# D5035-51.net
KiCad netlist of a schematic drawn in Altium Designer
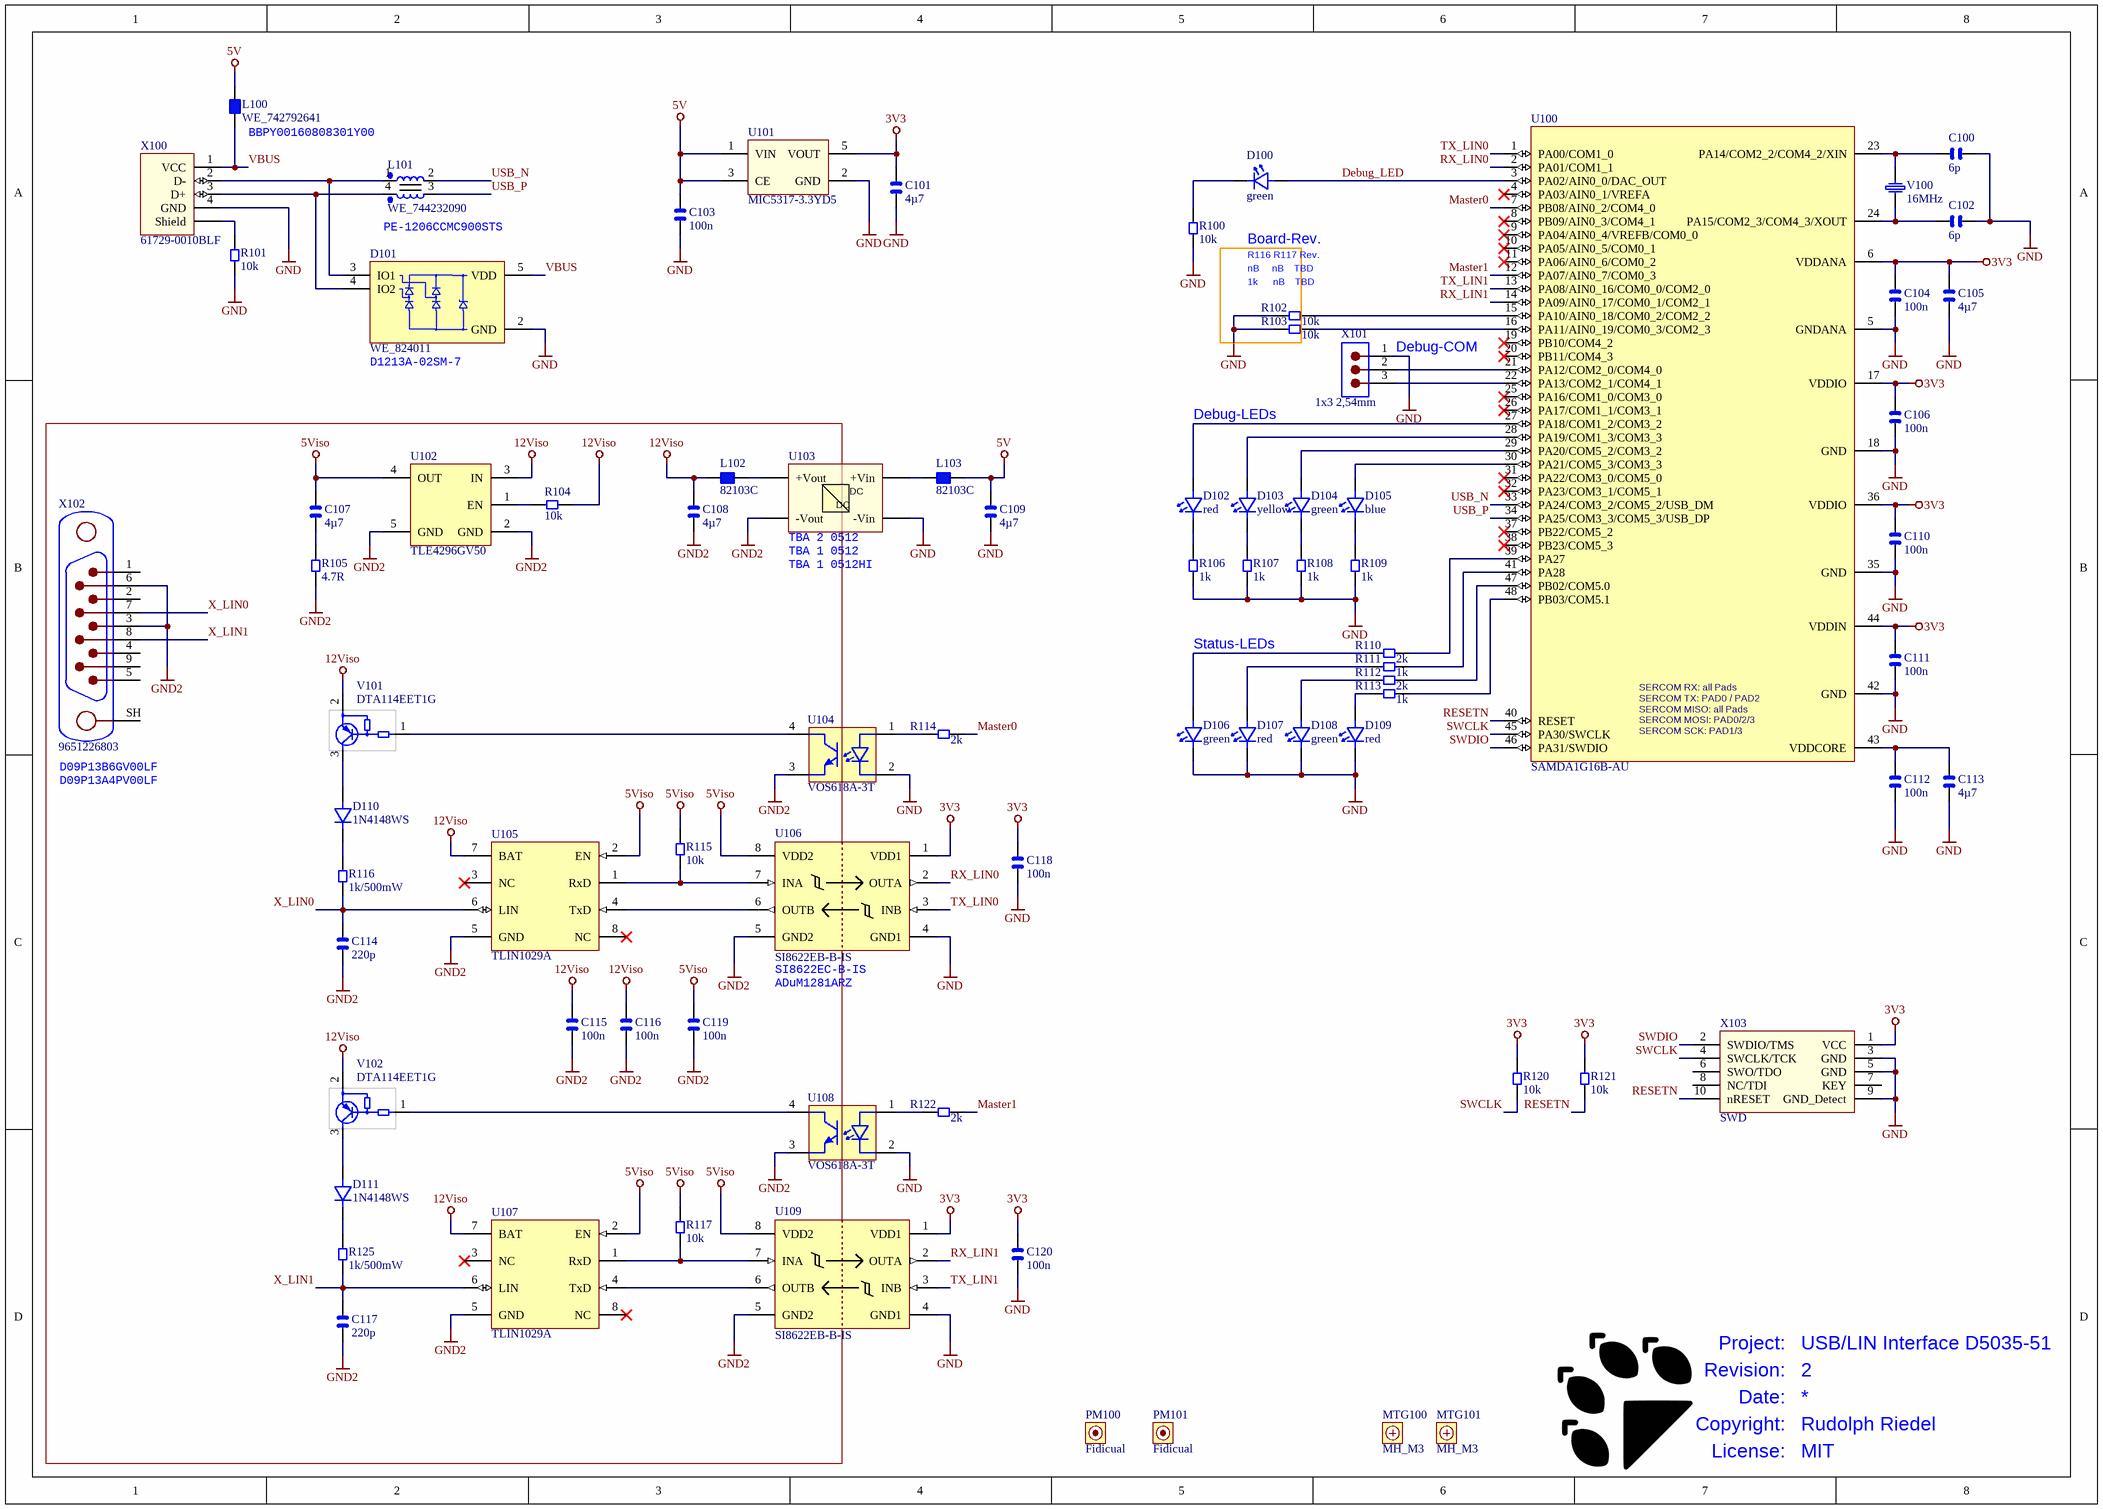
[diagram p0: D5035-51.SchDoc]

(export (version "E")
  (design (tool "Eeschema 10.0.6"))
  (components
    (comp (ref "C100")
      (value "6p")
      (footprint "CAPC1608X09L")
      (description "0603 Chip Capacitor")
      (fields (field (name "PART NUMBER") "CAPC_0603") (field (name "EDITOR") "rriedel"))
      (libsource (lib "HW-Labor_GF") (part "CAP_2_V2"))
    )
    (comp (ref "C101")
      (value "4µ7")
      (footprint "CAPC2012X14L")
      (description "0805 Chip Capacitor")
      (fields (field (name "PART NUMBER") "CAPC_0805") (field (name "EDITOR") "rriedel"))
      (libsource (lib "HW-Labor_GF") (part "CAP_2_V2"))
    )
    (comp (ref "C102")
      (value "6p")
      (footprint "CAPC1608X09L")
      (description "0603 Chip Capacitor")
      (fields (field (name "PART NUMBER") "CAPC_0603") (field (name "EDITOR") "rriedel"))
      (libsource (lib "HW-Labor_GF") (part "CAP_2_V2"))
    )
    (comp (ref "C103")
      (value "100n")
      (footprint "CAPC1608X09L")
      (description "0603 Chip Capacitor")
      (fields (field (name "PART NUMBER") "CAPC_0603") (field (name "EDITOR") "rriedel"))
      (libsource (lib "HW-Labor_GF") (part "CAP_2_V2"))
    )
    (comp (ref "C104")
      (value "100n")
      (footprint "CAPC1608X09L")
      (description "0603 Chip Capacitor")
      (fields (field (name "PART NUMBER") "CAPC_0603") (field (name "EDITOR") "rriedel"))
      (libsource (lib "HW-Labor_GF") (part "CAP_2_V2"))
    )
    (comp (ref "C105")
      (value "4µ7")
      (footprint "CAPC2012X14L")
      (description "0805 Chip Capacitor")
      (fields (field (name "PART NUMBER") "CAPC_0805") (field (name "EDITOR") "rriedel"))
      (libsource (lib "HW-Labor_GF") (part "CAP_2_V2"))
    )
    (comp (ref "C106")
      (value "100n")
      (footprint "CAPC1608X09L")
      (description "0603 Chip Capacitor")
      (fields (field (name "PART NUMBER") "CAPC_0603") (field (name "EDITOR") "rriedel"))
      (libsource (lib "HW-Labor_GF") (part "CAP_2_V2"))
    )
    (comp (ref "C107")
      (value "4µ7")
      (footprint "CAPC2012X14L")
      (description "0805 Chip Capacitor")
      (fields (field (name "PART NUMBER") "CAPC_0805") (field (name "EDITOR") "rriedel"))
      (libsource (lib "HW-Labor_GF") (part "CAP_2_V2"))
    )
    (comp (ref "C108")
      (value "4µ7")
      (footprint "CAPC2012X14L")
      (description "0805 Chip Capacitor")
      (fields (field (name "PART NUMBER") "CAPC_0805") (field (name "EDITOR") "rriedel"))
      (libsource (lib "HW-Labor_GF") (part "CAP_2_V2"))
    )
    (comp (ref "C109")
      (value "4µ7")
      (footprint "CAPC2012X14L")
      (description "0805 Chip Capacitor")
      (fields (field (name "PART NUMBER") "CAPC_0805") (field (name "EDITOR") "rriedel"))
      (libsource (lib "HW-Labor_GF") (part "CAP_2_V2"))
    )
    (comp (ref "C110")
      (value "100n")
      (footprint "CAPC1608X09L")
      (description "0603 Chip Capacitor")
      (fields (field (name "PART NUMBER") "CAPC_0603") (field (name "EDITOR") "rriedel"))
      (libsource (lib "HW-Labor_GF") (part "CAP_2_V2"))
    )
    (comp (ref "C111")
      (value "100n")
      (footprint "CAPC1608X09L")
      (description "0603 Chip Capacitor")
      (fields (field (name "PART NUMBER") "CAPC_0603") (field (name "EDITOR") "rriedel"))
      (libsource (lib "HW-Labor_GF") (part "CAP_2_V2"))
    )
    (comp (ref "C112")
      (value "100n")
      (footprint "CAPC1608X09L")
      (description "0603 Chip Capacitor")
      (fields (field (name "PART NUMBER") "CAPC_0603") (field (name "EDITOR") "rriedel"))
      (libsource (lib "HW-Labor_GF") (part "CAP_2_V2"))
    )
    (comp (ref "C113")
      (value "4µ7")
      (footprint "CAPC2012X14L")
      (description "0805 Chip Capacitor")
      (fields (field (name "PART NUMBER") "CAPC_0805") (field (name "EDITOR") "rriedel"))
      (libsource (lib "HW-Labor_GF") (part "CAP_2_V2"))
    )
    (comp (ref "C114")
      (value "220p")
      (footprint "CAPC2012X14L")
      (description "0805 Chip Capacitor")
      (fields (field (name "PART NUMBER") "CAPC_0805") (field (name "EDITOR") "rriedel"))
      (libsource (lib "HW-Labor_GF") (part "CAP_2_V2"))
    )
    (comp (ref "C115")
      (value "100n")
      (footprint "CAPC1608X09L")
      (description "0603 Chip Capacitor")
      (fields (field (name "PART NUMBER") "CAPC_0603") (field (name "EDITOR") "rriedel"))
      (libsource (lib "HW-Labor_GF") (part "CAP_2_V2"))
    )
    (comp (ref "C116")
      (value "100n")
      (footprint "CAPC1608X09L")
      (description "0603 Chip Capacitor")
      (fields (field (name "PART NUMBER") "CAPC_0603") (field (name "EDITOR") "rriedel"))
      (libsource (lib "HW-Labor_GF") (part "CAP_2_V2"))
    )
    (comp (ref "C117")
      (value "220p")
      (footprint "CAPC2012X14L")
      (description "0805 Chip Capacitor")
      (fields (field (name "PART NUMBER") "CAPC_0805") (field (name "EDITOR") "rriedel"))
      (libsource (lib "HW-Labor_GF") (part "CAP_2_V2"))
    )
    (comp (ref "C118")
      (value "100n")
      (footprint "CAPC1608X09L")
      (description "0603 Chip Capacitor")
      (fields (field (name "PART NUMBER") "CAPC_0603") (field (name "EDITOR") "rriedel"))
      (libsource (lib "HW-Labor_GF") (part "CAP_2_V2"))
    )
    (comp (ref "C119")
      (value "100n")
      (footprint "CAPC1608X09L")
      (description "0603 Chip Capacitor")
      (fields (field (name "PART NUMBER") "CAPC_0603") (field (name "EDITOR") "rriedel"))
      (libsource (lib "HW-Labor_GF") (part "CAP_2_V2"))
    )
    (comp (ref "C120")
      (value "100n")
      (footprint "CAPC1608X09L")
      (description "0603 Chip Capacitor")
      (fields (field (name "PART NUMBER") "CAPC_0603") (field (name "EDITOR") "rriedel"))
      (libsource (lib "HW-Labor_GF") (part "CAP_2_V2"))
    )
    (comp (ref "D100")
      (value "green")
      (footprint "DIOC1608X06N_LED")
      (description "LED, 0603")
      (fields (field (name "PART NUMBER") "LED_0603") (field (name "EDITOR") "rriedel"))
      (libsource (lib "HW-Labor_GF") (part "LED_generic"))
    )
    (comp (ref "D101")
      (value "WE_824011")
      (footprint "SOT95P280X110-5N")
      (description "TVS Diode Array WE-TVS")
      (fields
        (field (name "MANUFACTURER") "Wuerth")
        (field (name "DISTRIBUTOR_1_PART_NUMBER") "732-4465-1-ND")
        (field (name "EDITOR") "rriedel")
      )
      (libsource (lib "HW-Labor_GF") (part "WE-824011"))
    )
    (comp (ref "D102")
      (value "red")
      (footprint "DIOC1608X06N_LED")
      (description "LED, 0603")
      (fields (field (name "PART NUMBER") "LED_0603") (field (name "EDITOR") "rriedel"))
      (libsource (lib "HW-Labor_GF") (part "LED_generic"))
    )
    (comp (ref "D103")
      (value "yellow")
      (footprint "DIOC1608X06N_LED")
      (description "LED, 0603")
      (fields (field (name "PART NUMBER") "LED_0603") (field (name "EDITOR") "rriedel"))
      (libsource (lib "HW-Labor_GF") (part "LED_generic"))
    )
    (comp (ref "D104")
      (value "green")
      (footprint "DIOC1608X06N_LED")
      (description "LED, 0603")
      (fields (field (name "PART NUMBER") "LED_0603") (field (name "EDITOR") "rriedel"))
      (libsource (lib "HW-Labor_GF") (part "LED_generic"))
    )
    (comp (ref "D105")
      (value "blue")
      (footprint "DIOC1608X06N_LED")
      (description "LED, 0603")
      (fields (field (name "PART NUMBER") "LED_0603") (field (name "EDITOR") "rriedel"))
      (libsource (lib "HW-Labor_GF") (part "LED_generic"))
    )
    (comp (ref "D106")
      (value "green")
      (footprint "DIOC1608X06N_LED")
      (description "LED, 0603")
      (fields (field (name "PART NUMBER") "LED_0603") (field (name "EDITOR") "rriedel"))
      (libsource (lib "HW-Labor_GF") (part "LED_generic"))
    )
    (comp (ref "D107")
      (value "red")
      (footprint "DIOC1608X06N_LED")
      (description "LED, 0603")
      (fields (field (name "PART NUMBER") "LED_0603") (field (name "EDITOR") "rriedel"))
      (libsource (lib "HW-Labor_GF") (part "LED_generic"))
    )
    (comp (ref "D108")
      (value "green")
      (footprint "DIOC1608X06N_LED")
      (description "LED, 0603")
      (fields (field (name "PART NUMBER") "LED_0603") (field (name "EDITOR") "rriedel"))
      (libsource (lib "HW-Labor_GF") (part "LED_generic"))
    )
    (comp (ref "D109")
      (value "red")
      (footprint "DIOC1608X06N_LED")
      (description "LED, 0603")
      (fields (field (name "PART NUMBER") "LED_0603") (field (name "EDITOR") "rriedel"))
      (libsource (lib "HW-Labor_GF") (part "LED_generic"))
    )
    (comp (ref "D110")
      (value "1N4148WS")
      (footprint "SOD323")
      (description "Small Signal Diode IF 0.15A, VR 75V, SOD323F")
      (fields (field (name "DISTRIBUTOR_1_PART_NUMBER") "C2128") (field (name "EDITOR") "rriedel"))
      (libsource (lib "HW-Labor_GF") (part "Diode_A2_K1"))
    )
    (comp (ref "D111")
      (value "1N4148WS")
      (footprint "SOD323")
      (description "Small Signal Diode IF 0.15A, VR 75V, SOD323F")
      (fields (field (name "DISTRIBUTOR_1_PART_NUMBER") "C2128") (field (name "EDITOR") "rriedel"))
      (libsource (lib "HW-Labor_GF") (part "Diode_A2_K1"))
    )
    (comp (ref "L100")
      (value "WE_742792641")
      (footprint "INDC1608X06L")
      (description "SMT EMI suppression ferrite bead WE-CBF")
      (fields
        (field (name "MANUFACTURER") "Wuerth")
        (field (name "DISTRIBUTOR_1_PART_NUMBER") "732-1592-1-ND")
        (field (name "EDITOR") "rriedel")
      )
      (libsource (lib "HW-Labor_GF") (part "IND_2_V1"))
    )
    (comp (ref "L101")
      (value "WE_744232090")
      (footprint "WE_744232090")
      (description "SMD common mode noise suppressor WE-CNSW")
      (fields
        (field (name "MANUFACTURER") "Wuerth")
        (field (name "DISTRIBUTOR_1_PART_NUMBER") "732-1469-1-ND")
        (field (name "EDITOR") "rriedel")
      )
      (libsource (lib "HW-Labor_GF") (part "WE_744232090"))
    )
    (comp (ref "L102")
      (value "82103C")
      (footprint "Murata_8200C")
      (description "10µH, 0,5A, 400mR")
      (fields
        (field (name "MANUFACTURER") "Murata")
        (field (name "DISTRIBUTOR_1_PART_NUMBER") "811-2473-1-ND")
        (field (name "EDITOR") "rriedel")
      )
      (libsource (lib "HW-Labor_GF") (part "IND_2_V1"))
    )
    (comp (ref "L103")
      (value "82103C")
      (footprint "Murata_8200C")
      (description "10µH, 0,5A, 400mR")
      (fields
        (field (name "MANUFACTURER") "Murata")
        (field (name "DISTRIBUTOR_1_PART_NUMBER") "811-2473-1-ND")
        (field (name "EDITOR") "rriedel")
      )
      (libsource (lib "HW-Labor_GF") (part "IND_2_V1"))
    )
    (comp (ref "MTG100")
      (value "MH_M3")
      (footprint "HOLE_3_2MM")
      (description "Mounting-Hole for M3 screws")
      (fields (field (name "EDITOR") "rriedel"))
      (libsource (lib "HW-Labor_GF") (part "MTG_V1"))
    )
    (comp (ref "MTG101")
      (value "MH_M3")
      (footprint "HOLE_3_2MM")
      (description "Mounting-Hole for M3 screws")
      (fields (field (name "EDITOR") "rriedel"))
      (libsource (lib "HW-Labor_GF") (part "MTG_V1"))
    )
    (comp (ref "PM100")
      (value "Fidicual")
      (footprint "PM100")
      (fields (field (name "PART NUMBER") "PM100") (field (name "EDITOR") "rriedel"))
      (libsource (lib "HW-Labor_GF") (part "PM100"))
    )
    (comp (ref "PM101")
      (value "Fidicual")
      (footprint "PM100")
      (fields (field (name "PART NUMBER") "PM100") (field (name "EDITOR") "rriedel"))
      (libsource (lib "HW-Labor_GF") (part "PM100"))
    )
    (comp (ref "R100")
      (value "10k")
      (footprint "RESC1608X06L")
      (description "0603 Chip Resistor")
      (fields (field (name "PART NUMBER") "RESC_0603") (field (name "EDITOR") "rriedel"))
      (libsource (lib "HW-Labor_GF") (part "RES_2_V2"))
    )
    (comp (ref "R101")
      (value "10k")
      (footprint "RESC1608X06L")
      (description "0603 Chip Resistor")
      (fields (field (name "PART NUMBER") "RESC_0603") (field (name "EDITOR") "rriedel"))
      (libsource (lib "HW-Labor_GF") (part "RES_2_V2"))
    )
    (comp (ref "R102")
      (value "10k")
      (footprint "RESC1608X06L")
      (description "0603 Chip Resistor")
      (fields (field (name "PART NUMBER") "RESC_0603") (field (name "EDITOR") "rriedel"))
      (libsource (lib "HW-Labor_GF") (part "RES_2_V2"))
    )
    (comp (ref "R103")
      (value "10k")
      (footprint "RESC1608X06L")
      (description "0603 Chip Resistor")
      (fields (field (name "PART NUMBER") "RESC_0603") (field (name "EDITOR") "rriedel"))
      (libsource (lib "HW-Labor_GF") (part "RES_2_V2"))
    )
    (comp (ref "R104")
      (value "10k")
      (footprint "RESC1608X06L")
      (description "0603 Chip Resistor")
      (fields (field (name "PART NUMBER") "RESC_0603") (field (name "EDITOR") "rriedel"))
      (libsource (lib "HW-Labor_GF") (part "RES_2_V2"))
    )
    (comp (ref "R105")
      (value "4.7R")
      (footprint "RESC1608X06L")
      (description "0603 Chip Resistor")
      (fields (field (name "PART NUMBER") "RESC_0603") (field (name "EDITOR") "rriedel"))
      (libsource (lib "HW-Labor_GF") (part "RES_2_V2"))
    )
    (comp (ref "R106")
      (value "1k")
      (footprint "RESC1608X06L")
      (description "0603 Chip Resistor")
      (fields (field (name "PART NUMBER") "RESC_0603") (field (name "EDITOR") "rriedel"))
      (libsource (lib "HW-Labor_GF") (part "RES_2_V2"))
    )
    (comp (ref "R107")
      (value "1k")
      (footprint "RESC1608X06L")
      (description "0603 Chip Resistor")
      (fields (field (name "PART NUMBER") "RESC_0603") (field (name "EDITOR") "rriedel"))
      (libsource (lib "HW-Labor_GF") (part "RES_2_V2"))
    )
    (comp (ref "R108")
      (value "1k")
      (footprint "RESC1608X06L")
      (description "0603 Chip Resistor")
      (fields (field (name "PART NUMBER") "RESC_0603") (field (name "EDITOR") "rriedel"))
      (libsource (lib "HW-Labor_GF") (part "RES_2_V2"))
    )
    (comp (ref "R109")
      (value "1k")
      (footprint "RESC1608X06L")
      (description "0603 Chip Resistor")
      (fields (field (name "PART NUMBER") "RESC_0603") (field (name "EDITOR") "rriedel"))
      (libsource (lib "HW-Labor_GF") (part "RES_2_V2"))
    )
    (comp (ref "R110")
      (value "2k")
      (footprint "RESC1608X06L")
      (description "0603 Chip Resistor")
      (fields (field (name "PART NUMBER") "RESC_0603") (field (name "EDITOR") "rriedel"))
      (libsource (lib "HW-Labor_GF") (part "RES_2_V2"))
    )
    (comp (ref "R111")
      (value "1k")
      (footprint "RESC1608X06L")
      (description "0603 Chip Resistor")
      (fields (field (name "PART NUMBER") "RESC_0603") (field (name "EDITOR") "rriedel"))
      (libsource (lib "HW-Labor_GF") (part "RES_2_V2"))
    )
    (comp (ref "R112")
      (value "2k")
      (footprint "RESC1608X06L")
      (description "0603 Chip Resistor")
      (fields (field (name "PART NUMBER") "RESC_0603") (field (name "EDITOR") "rriedel"))
      (libsource (lib "HW-Labor_GF") (part "RES_2_V2"))
    )
    (comp (ref "R113")
      (value "1k")
      (footprint "RESC1608X06L")
      (description "0603 Chip Resistor")
      (fields (field (name "PART NUMBER") "RESC_0603") (field (name "EDITOR") "rriedel"))
      (libsource (lib "HW-Labor_GF") (part "RES_2_V2"))
    )
    (comp (ref "R114")
      (value "2k")
      (footprint "RESC1608X06L")
      (description "0603 Chip Resistor")
      (fields (field (name "PART NUMBER") "RESC_0603") (field (name "EDITOR") "rriedel"))
      (libsource (lib "HW-Labor_GF") (part "RES_2_V2"))
    )
    (comp (ref "R115")
      (value "10k")
      (footprint "RESC1608X06L")
      (description "0603 Chip Resistor")
      (fields (field (name "PART NUMBER") "RESC_0603") (field (name "EDITOR") "rriedel"))
      (libsource (lib "HW-Labor_GF") (part "RES_2_V2"))
    )
    (comp (ref "R116")
      (value "1k/500mW")
      (footprint "RESC2012X06L")
      (description "0805 Chip Resistor")
      (fields (field (name "PART NUMBER") "RESC_0805") (field (name "EDITOR") "rriedel"))
      (libsource (lib "HW-Labor_GF") (part "RES_2_V2"))
    )
    (comp (ref "R117")
      (value "10k")
      (footprint "RESC1608X06L")
      (description "0603 Chip Resistor")
      (fields (field (name "PART NUMBER") "RESC_0603") (field (name "EDITOR") "rriedel"))
      (libsource (lib "HW-Labor_GF") (part "RES_2_V2"))
    )
    (comp (ref "R120")
      (value "10k")
      (footprint "RESC1608X06L")
      (description "0603 Chip Resistor")
      (fields (field (name "PART NUMBER") "RESC_0603") (field (name "EDITOR") "rriedel"))
      (libsource (lib "HW-Labor_GF") (part "RES_2_V2"))
    )
    (comp (ref "R121")
      (value "10k")
      (footprint "RESC1608X06L")
      (description "0603 Chip Resistor")
      (fields (field (name "PART NUMBER") "RESC_0603") (field (name "EDITOR") "rriedel"))
      (libsource (lib "HW-Labor_GF") (part "RES_2_V2"))
    )
    (comp (ref "R122")
      (value "2k")
      (footprint "RESC1608X06L")
      (description "0603 Chip Resistor")
      (fields (field (name "PART NUMBER") "RESC_0603") (field (name "EDITOR") "rriedel"))
      (libsource (lib "HW-Labor_GF") (part "RES_2_V2"))
    )
    (comp (ref "R125")
      (value "1k/500mW")
      (footprint "RESC2012X06L")
      (description "0805 Chip Resistor")
      (fields (field (name "PART NUMBER") "RESC_0805") (field (name "EDITOR") "rriedel"))
      (libsource (lib "HW-Labor_GF") (part "RES_2_V2"))
    )
    (comp (ref "U100")
      (value "SAMDA1G16B-AU")
      (footprint "TQFP50P900X900X120-48N")
      (description "32-bit Microcontroller, 48MHz Cortex M0, 64k FLASH,  USB, -40…85°C")
      (fields
        (field (name "MANUFACTURER") "Microchip")
        (field (name "DISTRIBUTOR_1_PART_NUMBER") "556-ATSAMDA1G16B-ABT")
        (field (name "EDITOR") "rriedel")
      )
      (libsource (lib "HW-Labor_GF") (part "ATSAMDA1G1xB"))
    )
    (comp (ref "U101")
      (value "MIC5317-3.3YD5")
      (footprint "SOT95P280X110-5N")
      (description "100 mA LDO,  Vout= 3,3V, -40°C..125°C")
      (fields
        (field (name "PART NUMBER") "MIC5233-3.3")
        (field (name "MANUFACTURER") "Microchip")
        (field (name "EDITOR") "rriedel")
      )
      (libsource (lib "HW-Labor_GF") (part "LDO_SOT23-5"))
    )
    (comp (ref "U102")
      (value "TLE4296GV50")
      (footprint "INF-PG-SCT595V")
      (description "30 mA LDO, Vout = 5,0V, 4%")
      (fields (field (name "MANUFACTURER") "Infineon") (field (name "EDITOR") "rriedel"))
      (libsource (lib "HW-Labor_GF") (part "TLE4295GVxx"))
    )
    (comp (ref "U103")
      (value "~")
      (footprint "TBA1/TBA2")
      (description "Isolated Single Output DC-DC Converters 5V/12V")
      (fields (field (name "PART NUMBER") "TBA 2-0512") (field (name "EDITOR") "rriedel"))
      (libsource (lib "HW-Labor_GF") (part "MER1SxxxxC"))
    )
    (comp (ref "U104")
      (value "VOS618A-3T")
      (footprint "SSOP-4")
      (description "Optocoupler, Phototransistor Output, Low Input Current, SSOP-4")
      (fields
        (field (name "MANUFACTURER") "Vishay")
        (field (name "DISTRIBUTOR_1_PART_NUMBER") "VOS618A-3TCT-ND‎")
        (field (name "EDITOR") "rriedel")
      )
      (libsource (lib "HW-Labor_GF") (part "VOS618A"))
    )
    (comp (ref "U105")
      (value "TLIN1029A")
      (footprint "SOIC127P600X175-8N")
      (description "LIN transceiver")
      (fields
        (field (name "MANUFACTURER") "TI")
        (field (name "DISTRIBUTOR_1_PART_NUMBER") "595-TLIN1029ADRQ1")
        (field (name "EDITOR") "rriedel")
      )
      (libsource (lib "HW-Labor_GF") (part "TLIN1029A"))
    )
    (comp (ref "U106")
      (value "SI8622EB-B-IS")
      (footprint "SOIC127P600X175-8N")
      (description "Dual channel digital isolator, 150Mbit, 2,5kV")
      (fields
        (field (name "MANUFACTURER") "Silicon Labs")
        (field (name "DISTRIBUTOR_1_PART_NUMBER") "336-5209-1-ND")
        (field (name "EDITOR") "rriedel")
      )
      (libsource (lib "HW-Labor_GF") (part "SI8622"))
    )
    (comp (ref "U107")
      (value "TLIN1029A")
      (footprint "SOIC127P600X175-8N")
      (description "LIN transceiver")
      (fields
        (field (name "MANUFACTURER") "TI")
        (field (name "DISTRIBUTOR_1_PART_NUMBER") "595-TLIN1029ADRQ1")
        (field (name "EDITOR") "rriedel")
      )
      (libsource (lib "HW-Labor_GF") (part "TLIN1029A"))
    )
    (comp (ref "U108")
      (value "VOS618A-3T")
      (footprint "SSOP-4")
      (description "Optocoupler, Phototransistor Output, Low Input Current, SSOP-4")
      (fields
        (field (name "MANUFACTURER") "Vishay")
        (field (name "DISTRIBUTOR_1_PART_NUMBER") "VOS618A-3TCT-ND‎")
        (field (name "EDITOR") "rriedel")
      )
      (libsource (lib "HW-Labor_GF") (part "VOS618A"))
    )
    (comp (ref "U109")
      (value "SI8622EB-B-IS")
      (footprint "SOIC127P600X175-8N")
      (description "Dual channel digital isolator, 150Mbit, 2,5kV")
      (fields
        (field (name "MANUFACTURER") "Silicon Labs")
        (field (name "DISTRIBUTOR_1_PART_NUMBER") "336-5209-1-ND")
        (field (name "EDITOR") "rriedel")
      )
      (libsource (lib "HW-Labor_GF") (part "SI8622"))
    )
    (comp (ref "V100")
      (value "16MHz")
      (footprint "NX3225Gx")
      (description "16.000MHz Crystal SMD, 3.2x2.5mm, 8pF, 50ppm,  -40..+150°C")
      (fields
        (field (name "PART NUMBER") "NX3225GB-16.000000MHZ")
        (field (name "MANUFACTURER") "NDK")
        (field (name "EDITOR") "rriedel")
      )
      (libsource (lib "HW-Labor_GF") (part "XTAL_2_V1"))
    )
    (comp (ref "V101")
      (value "DTA114EET1G")
      (footprint "SOT50P162X60-3N")
      (description "PNP Transistor with Resistors (10kΩ, 10kΩ)  VCE= 50V, IC=100mA, SOT23, AEC Q101")
      (fields (field (name "EDITOR") "rriedel"))
      (libsource (lib "HW-Labor_GF") (part "PNP_Digital"))
    )
    (comp (ref "V102")
      (value "DTA114EET1G")
      (footprint "SOT50P162X60-3N")
      (description "PNP Transistor with Resistors (10kΩ, 10kΩ)  VCE= 50V, IC=100mA, SOT23, AEC Q101")
      (fields (field (name "EDITOR") "rriedel"))
      (libsource (lib "HW-Labor_GF") (part "PNP_Digital"))
    )
    (comp (ref "X100")
      (value "61729-0010BLF")
      (footprint "61729-xxxxxLF")
      (description "USB-B socket, THT")
      (fields
        (field (name "MANUFACTURER") "Amphenol")
        (field (name "DISTRIBUTOR_1_PART_NUMBER") "609-1039-ND")
        (field (name "EDITOR") "rriedel")
      )
      (libsource (lib "HW-Labor_GF") (part "USB"))
    )
    (comp (ref "X101")
      (value "1x3 2,54mm")
      (footprint "PINH_1x03_2_54mm")
      (description "Pin-Header 2,54 mm 3pins")
      (fields (field (name "PART NUMBER") "PINH_1x3_2_54") (field (name "EDITOR") "rriedel"))
      (libsource (lib "HW-Labor_GF") (part "CONM_1x3_V2"))
    )
    (comp (ref "X102")
      (value "9651226803")
      (footprint "09651226803")
      (description "D-Sub, 9 pin, male, right angle")
      (fields
        (field (name "MANUFACTURER") "Harting")
        (field (name "DISTRIBUTOR_1_PART_NUMBER") "2752007")
        (field (name "EDITOR") "rriedel")
      )
      (libsource (lib "HW-Labor_GF") (part "D_Sub_9_Male"))
    )
    (comp (ref "X103")
      (value "SWD")
      (footprint "FTSH-105-01-L-DV-K")
      (description "ARM Debug-Header 2x5 1,27 mm")
      (fields (field (name "EDITOR") "rriedel"))
      (libsource (lib "HW-Labor_GF") (part "SWD"))
    )
  )
  (nets
    (net (code "1") (name "/Debug_LED") (class "Default")
      (node (ref "D100") (pin "2") (pinfunction "2_2") (pintype "passive"))
      (node (ref "U100") (pin "3") (pinfunction "PA02/AIN0_0/DAC_OUT_3") (pintype "bidirectional"))
    )
    (net (code "2") (name "/Master0") (class "Default")
      (node (ref "R114") (pin "1") (pinfunction "1_1") (pintype "passive"))
      (node (ref "U100") (pin "7") (pinfunction "PB08/AIN0_2/COM4_0_7") (pintype "bidirectional"))
    )
    (net (code "3") (name "/Master1") (class "Default")
      (node (ref "R122") (pin "1") (pinfunction "1_1") (pintype "passive"))
      (node (ref "U100") (pin "12") (pinfunction "PA07/AIN0_7/COM0_3_12") (pintype "bidirectional"))
    )
    (net (code "4") (name "/RESETN") (class "Default")
      (node (ref "R121") (pin "2") (pinfunction "2_2") (pintype "passive"))
      (node (ref "U100") (pin "40") (pinfunction "RESET_40") (pintype "bidirectional"))
      (node (ref "X103") (pin "10") (pinfunction "nRESET_10") (pintype "passive"))
    )
    (net (code "5") (name "/RX_LIN0") (class "Default")
      (node (ref "U100") (pin "2") (pinfunction "PA01/COM1_1_2") (pintype "bidirectional"))
      (node (ref "U106") (pin "2") (pinfunction "OUTA_2") (pintype "output"))
    )
    (net (code "6") (name "/RX_LIN1") (class "Default")
      (node (ref "U100") (pin "14") (pinfunction "PA09/AIN0_17/COM0_1/COM2_1_14") (pintype "bidirectional"))
      (node (ref "U109") (pin "2") (pinfunction "OUTA_2") (pintype "output"))
    )
    (net (code "7") (name "/SWCLK") (class "Default")
      (node (ref "R120") (pin "2") (pinfunction "2_2") (pintype "passive"))
      (node (ref "U100") (pin "45") (pinfunction "PA30/SWCLK_45") (pintype "bidirectional"))
      (node (ref "X103") (pin "4") (pinfunction "SWCLK/TCK_4") (pintype "passive"))
    )
    (net (code "8") (name "/SWDIO") (class "Default")
      (node (ref "U100") (pin "46") (pinfunction "PA31/SWDIO_46") (pintype "bidirectional"))
      (node (ref "X103") (pin "2") (pinfunction "SWDIO/TMS_2") (pintype "passive"))
    )
    (net (code "9") (name "/TX_LIN0") (class "Default")
      (node (ref "U100") (pin "1") (pinfunction "PA00/COM1_0_1") (pintype "bidirectional"))
      (node (ref "U106") (pin "3") (pinfunction "INB_3") (pintype "input"))
    )
    (net (code "10") (name "/TX_LIN1") (class "Default")
      (node (ref "U100") (pin "13") (pinfunction "PA08/AIN0_16/COM0_0/COM2_0_13") (pintype "bidirectional"))
      (node (ref "U109") (pin "3") (pinfunction "INB_3") (pintype "input"))
    )
    (net (code "11") (name "/USB_N") (class "Default")
      (node (ref "L101") (pin "2") (pinfunction "2_2") (pintype "passive"))
      (node (ref "U100") (pin "33") (pinfunction "PA24/COM3_2/COM5_2/USB_DM_33") (pintype "bidirectional"))
    )
    (net (code "12") (name "/USB_P") (class "Default")
      (node (ref "L101") (pin "3") (pinfunction "3_3") (pintype "passive"))
      (node (ref "U100") (pin "34") (pinfunction "PA25/COM3_3/COM5_3/USB_DP_34") (pintype "bidirectional"))
    )
    (net (code "13") (name "/VBUS") (class "Default")
      (node (ref "D101") (pin "5") (pinfunction "VDD_5") (pintype "passive"))
      (node (ref "L100") (pin "1") (pinfunction "1_1") (pintype "passive"))
      (node (ref "X100") (pin "1") (pinfunction "VCC_1") (pintype "power_in"))
    )
    (net (code "14") (name "/X_LIN0") (class "Default")
      (node (ref "C114") (pin "2") (pinfunction "2_2") (pintype "passive"))
      (node (ref "R116") (pin "1") (pinfunction "1_1") (pintype "passive"))
      (node (ref "U105") (pin "6") (pinfunction "LIN_6") (pintype "bidirectional"))
      (node (ref "X102") (pin "7") (pinfunction "7_7") (pintype "passive"))
    )
    (net (code "15") (name "/X_LIN1") (class "Default")
      (node (ref "C117") (pin "2") (pinfunction "2_2") (pintype "passive"))
      (node (ref "R125") (pin "1") (pinfunction "1_1") (pintype "passive"))
      (node (ref "U107") (pin "6") (pinfunction "LIN_6") (pintype "bidirectional"))
      (node (ref "X102") (pin "8") (pinfunction "8_8") (pintype "passive"))
    )
    (net (code "16") (name "3V3") (class "Default")
      (node (ref "C101") (pin "2") (pinfunction "2_2") (pintype "passive"))
      (node (ref "C104") (pin "2") (pinfunction "2_2") (pintype "passive"))
      (node (ref "C105") (pin "2") (pinfunction "2_2") (pintype "passive"))
      (node (ref "C106") (pin "2") (pinfunction "2_2") (pintype "passive"))
      (node (ref "C110") (pin "2") (pinfunction "2_2") (pintype "passive"))
      (node (ref "C111") (pin "2") (pinfunction "2_2") (pintype "passive"))
      (node (ref "C118") (pin "2") (pinfunction "2_2") (pintype "passive"))
      (node (ref "C120") (pin "2") (pinfunction "2_2") (pintype "passive"))
      (node (ref "R120") (pin "1") (pinfunction "1_1") (pintype "passive"))
      (node (ref "R121") (pin "1") (pinfunction "1_1") (pintype "passive"))
      (node (ref "U100") (pin "17") (pinfunction "VDDIO_17") (pintype "power_in"))
      (node (ref "U100") (pin "36") (pinfunction "VDDIO_36") (pintype "power_in"))
      (node (ref "U100") (pin "44") (pinfunction "VDDIN_44") (pintype "power_in"))
      (node (ref "U100") (pin "6") (pinfunction "VDDANA_6") (pintype "power_in"))
      (node (ref "U101") (pin "5") (pinfunction "VOUT_5") (pintype "passive"))
      (node (ref "U106") (pin "1") (pinfunction "VDD1_1") (pintype "power_in"))
      (node (ref "U109") (pin "1") (pinfunction "VDD1_1") (pintype "power_in"))
      (node (ref "X103") (pin "1") (pinfunction "VCC_1") (pintype "power_in"))
    )
    (net (code "17") (name "5V") (class "Default")
      (node (ref "C103") (pin "2") (pinfunction "2_2") (pintype "passive"))
      (node (ref "C109") (pin "2") (pinfunction "2_2") (pintype "passive"))
      (node (ref "L100") (pin "2") (pinfunction "2_2") (pintype "passive"))
      (node (ref "L103") (pin "1") (pinfunction "1_1") (pintype "passive"))
      (node (ref "U101") (pin "1") (pinfunction "VIN_1") (pintype "passive"))
      (node (ref "U101") (pin "3") (pinfunction "CE_3") (pintype "passive"))
    )
    (net (code "18") (name "5Viso") (class "Default")
      (node (ref "C107") (pin "2") (pinfunction "2_2") (pintype "passive"))
      (node (ref "C119") (pin "2") (pinfunction "2_2") (pintype "passive"))
      (node (ref "R115") (pin "1") (pinfunction "1_1") (pintype "passive"))
      (node (ref "R117") (pin "1") (pinfunction "1_1") (pintype "passive"))
      (node (ref "U102") (pin "4") (pinfunction "OUT_4") (pintype "passive"))
      (node (ref "U105") (pin "2") (pinfunction "EN_2") (pintype "input"))
      (node (ref "U106") (pin "8") (pinfunction "VDD2_8") (pintype "power_in"))
      (node (ref "U107") (pin "2") (pinfunction "EN_2") (pintype "input"))
      (node (ref "U109") (pin "8") (pinfunction "VDD2_8") (pintype "power_in"))
    )
    (net (code "19") (name "12Viso") (class "Default")
      (node (ref "C108") (pin "2") (pinfunction "2_2") (pintype "passive"))
      (node (ref "C115") (pin "2") (pinfunction "2_2") (pintype "passive"))
      (node (ref "C116") (pin "2") (pinfunction "2_2") (pintype "passive"))
      (node (ref "L102") (pin "2") (pinfunction "2_2") (pintype "passive"))
      (node (ref "R104") (pin "2") (pinfunction "2_2") (pintype "passive"))
      (node (ref "U102") (pin "3") (pinfunction "IN_3") (pintype "passive"))
      (node (ref "U105") (pin "7") (pinfunction "BAT_7") (pintype "power_in"))
      (node (ref "U107") (pin "7") (pinfunction "BAT_7") (pintype "power_in"))
      (node (ref "V101") (pin "2") (pinfunction "2_2") (pintype "passive"))
      (node (ref "V102") (pin "2") (pinfunction "2_2") (pintype "passive"))
    )
    (net (code "20") (name "GND") (class "Default")
      (node (ref "C100") (pin "2") (pinfunction "2_2") (pintype "passive"))
      (node (ref "C101") (pin "1") (pinfunction "1_1") (pintype "passive"))
      (node (ref "C102") (pin "2") (pinfunction "2_2") (pintype "passive"))
      (node (ref "C103") (pin "1") (pinfunction "1_1") (pintype "passive"))
      (node (ref "C104") (pin "1") (pinfunction "1_1") (pintype "passive"))
      (node (ref "C105") (pin "1") (pinfunction "1_1") (pintype "passive"))
      (node (ref "C106") (pin "1") (pinfunction "1_1") (pintype "passive"))
      (node (ref "C109") (pin "1") (pinfunction "1_1") (pintype "passive"))
      (node (ref "C110") (pin "1") (pinfunction "1_1") (pintype "passive"))
      (node (ref "C111") (pin "1") (pinfunction "1_1") (pintype "passive"))
      (node (ref "C112") (pin "1") (pinfunction "1_1") (pintype "passive"))
      (node (ref "C113") (pin "1") (pinfunction "1_1") (pintype "passive"))
      (node (ref "C118") (pin "1") (pinfunction "1_1") (pintype "passive"))
      (node (ref "C120") (pin "1") (pinfunction "1_1") (pintype "passive"))
      (node (ref "D101") (pin "2") (pinfunction "GND_2") (pintype "passive"))
      (node (ref "D106") (pin "1") (pinfunction "1_1") (pintype "passive"))
      (node (ref "D107") (pin "1") (pinfunction "1_1") (pintype "passive"))
      (node (ref "D108") (pin "1") (pinfunction "1_1") (pintype "passive"))
      (node (ref "D109") (pin "1") (pinfunction "1_1") (pintype "passive"))
      (node (ref "R100") (pin "1") (pinfunction "1_1") (pintype "passive"))
      (node (ref "R101") (pin "1") (pinfunction "1_1") (pintype "passive"))
      (node (ref "R102") (pin "2") (pinfunction "2_2") (pintype "passive"))
      (node (ref "R103") (pin "2") (pinfunction "2_2") (pintype "passive"))
      (node (ref "R106") (pin "1") (pinfunction "1_1") (pintype "passive"))
      (node (ref "R107") (pin "1") (pinfunction "1_1") (pintype "passive"))
      (node (ref "R108") (pin "1") (pinfunction "1_1") (pintype "passive"))
      (node (ref "R109") (pin "1") (pinfunction "1_1") (pintype "passive"))
      (node (ref "U100") (pin "18") (pinfunction "GND_18") (pintype "power_in"))
      (node (ref "U100") (pin "35") (pinfunction "GND_35") (pintype "power_in"))
      (node (ref "U100") (pin "42") (pinfunction "GND_42") (pintype "power_in"))
      (node (ref "U100") (pin "5") (pinfunction "GNDANA_5") (pintype "power_in"))
      (node (ref "U101") (pin "2") (pinfunction "GND_2") (pintype "passive"))
      (node (ref "U103") (pin "2") (pinfunction "-Vin_2") (pintype "power_in"))
      (node (ref "U104") (pin "2") (pinfunction "C_2") (pintype "passive"))
      (node (ref "U106") (pin "4") (pinfunction "GND1_4") (pintype "power_in"))
      (node (ref "U108") (pin "2") (pinfunction "C_2") (pintype "passive"))
      (node (ref "U109") (pin "4") (pinfunction "GND1_4") (pintype "power_in"))
      (node (ref "X100") (pin "4") (pinfunction "GND_4") (pintype "power_in"))
      (node (ref "X101") (pin "1") (pinfunction "1_1") (pintype "passive"))
      (node (ref "X103") (pin "3") (pinfunction "GND_3") (pintype "power_in"))
      (node (ref "X103") (pin "5") (pinfunction "GND_5") (pintype "power_in"))
      (node (ref "X103") (pin "9") (pinfunction "GND_Detect_9") (pintype "power_in"))
    )
    (net (code "21") (name "GND2") (class "Default")
      (node (ref "C108") (pin "1") (pinfunction "1_1") (pintype "passive"))
      (node (ref "C114") (pin "1") (pinfunction "1_1") (pintype "passive"))
      (node (ref "C115") (pin "1") (pinfunction "1_1") (pintype "passive"))
      (node (ref "C116") (pin "1") (pinfunction "1_1") (pintype "passive"))
      (node (ref "C117") (pin "1") (pinfunction "1_1") (pintype "passive"))
      (node (ref "C119") (pin "1") (pinfunction "1_1") (pintype "passive"))
      (node (ref "R105") (pin "2") (pinfunction "2_2") (pintype "passive"))
      (node (ref "U102") (pin "2") (pinfunction "GND_2") (pintype "passive"))
      (node (ref "U102") (pin "5") (pinfunction "GND_5") (pintype "passive"))
      (node (ref "U103") (pin "4") (pinfunction "-Vout_4") (pintype "power_in"))
      (node (ref "U104") (pin "3") (pinfunction "E_3") (pintype "passive"))
      (node (ref "U105") (pin "5") (pinfunction "GND_5") (pintype "power_in"))
      (node (ref "U106") (pin "5") (pinfunction "GND2_5") (pintype "power_in"))
      (node (ref "U107") (pin "5") (pinfunction "GND_5") (pintype "power_in"))
      (node (ref "U108") (pin "3") (pinfunction "E_3") (pintype "passive"))
      (node (ref "U109") (pin "5") (pinfunction "GND2_5") (pintype "power_in"))
      (node (ref "X102") (pin "3") (pinfunction "3_3") (pintype "passive"))
      (node (ref "X102") (pin "6") (pinfunction "6_6") (pintype "passive"))
    )
    (net (code "22") (name "Net-(C107-Pad1)") (class "Default")
      (node (ref "C107") (pin "1") (pinfunction "1_1") (pintype "passive"))
      (node (ref "R105") (pin "1") (pinfunction "1_1") (pintype "passive"))
    )
    (net (code "23") (name "Net-(D100-Pad1)") (class "Default")
      (node (ref "D100") (pin "1") (pinfunction "1_1") (pintype "passive"))
      (node (ref "R100") (pin "2") (pinfunction "2_2") (pintype "passive"))
    )
    (net (code "24") (name "Net-(D101-IO1)") (class "Default")
      (node (ref "D101") (pin "3") (pinfunction "IO1_3") (pintype "passive"))
      (node (ref "L101") (pin "1") (pinfunction "1_1") (pintype "passive"))
      (node (ref "X100") (pin "2") (pinfunction "D-_2") (pintype "bidirectional"))
    )
    (net (code "25") (name "Net-(D101-IO2)") (class "Default")
      (node (ref "D101") (pin "4") (pinfunction "IO2_4") (pintype "passive"))
      (node (ref "L101") (pin "4") (pinfunction "4_4") (pintype "passive"))
      (node (ref "X100") (pin "3") (pinfunction "D+_3") (pintype "bidirectional"))
    )
    (net (code "26") (name "Net-(D102-Pad1)") (class "Default")
      (node (ref "D102") (pin "1") (pinfunction "1_1") (pintype "passive"))
      (node (ref "R106") (pin "2") (pinfunction "2_2") (pintype "passive"))
    )
    (net (code "27") (name "Net-(D103-Pad1)") (class "Default")
      (node (ref "D103") (pin "1") (pinfunction "1_1") (pintype "passive"))
      (node (ref "R107") (pin "2") (pinfunction "2_2") (pintype "passive"))
    )
    (net (code "28") (name "Net-(D104-Pad1)") (class "Default")
      (node (ref "D104") (pin "1") (pinfunction "1_1") (pintype "passive"))
      (node (ref "R108") (pin "2") (pinfunction "2_2") (pintype "passive"))
    )
    (net (code "29") (name "Net-(D105-Pad1)") (class "Default")
      (node (ref "D105") (pin "1") (pinfunction "1_1") (pintype "passive"))
      (node (ref "R109") (pin "2") (pinfunction "2_2") (pintype "passive"))
    )
    (net (code "30") (name "Net-(D106-Pad2)") (class "Default")
      (node (ref "D106") (pin "2") (pinfunction "2_2") (pintype "passive"))
      (node (ref "R110") (pin "1") (pinfunction "1_1") (pintype "passive"))
    )
    (net (code "31") (name "Net-(D107-Pad2)") (class "Default")
      (node (ref "D107") (pin "2") (pinfunction "2_2") (pintype "passive"))
      (node (ref "R111") (pin "1") (pinfunction "1_1") (pintype "passive"))
    )
    (net (code "32") (name "Net-(D108-Pad2)") (class "Default")
      (node (ref "D108") (pin "2") (pinfunction "2_2") (pintype "passive"))
      (node (ref "R112") (pin "1") (pinfunction "1_1") (pintype "passive"))
    )
    (net (code "33") (name "Net-(D109-Pad2)") (class "Default")
      (node (ref "D109") (pin "2") (pinfunction "2_2") (pintype "passive"))
      (node (ref "R113") (pin "1") (pinfunction "1_1") (pintype "passive"))
    )
    (net (code "34") (name "Net-(D110-Pad1)") (class "Default")
      (node (ref "D110") (pin "1") (pinfunction "1_1") (pintype "passive"))
      (node (ref "R116") (pin "2") (pinfunction "2_2") (pintype "passive"))
    )
    (net (code "35") (name "Net-(D110-Pad2)") (class "Default")
      (node (ref "D110") (pin "2") (pinfunction "2_2") (pintype "passive"))
      (node (ref "V101") (pin "3") (pinfunction "3_3") (pintype "passive"))
    )
    (net (code "36") (name "Net-(D111-Pad1)") (class "Default")
      (node (ref "D111") (pin "1") (pinfunction "1_1") (pintype "passive"))
      (node (ref "R125") (pin "2") (pinfunction "2_2") (pintype "passive"))
    )
    (net (code "37") (name "Net-(D111-Pad2)") (class "Default")
      (node (ref "D111") (pin "2") (pinfunction "2_2") (pintype "passive"))
      (node (ref "V102") (pin "3") (pinfunction "3_3") (pintype "passive"))
    )
    (net (code "38") (name "Net-(U100-PA10{slash}AIN0_18{slash}COM0_2{slash}COM2_2)") (class "Default")
      (node (ref "R102") (pin "1") (pinfunction "1_1") (pintype "passive"))
      (node (ref "U100") (pin "15") (pinfunction "PA10/AIN0_18/COM0_2/COM2_2_15") (pintype "bidirectional"))
    )
    (net (code "39") (name "Net-(U100-PA11{slash}AIN0_19{slash}COM0_3{slash}COM2_3)") (class "Default")
      (node (ref "R103") (pin "1") (pinfunction "1_1") (pintype "passive"))
      (node (ref "U100") (pin "16") (pinfunction "PA11/AIN0_19/COM0_3/COM2_3_16") (pintype "bidirectional"))
    )
    (net (code "40") (name "Net-(U100-PA12{slash}COM2_0{slash}COM4_0)") (class "Default")
      (node (ref "U100") (pin "21") (pinfunction "PA12/COM2_0/COM4_0_21") (pintype "bidirectional"))
      (node (ref "X101") (pin "2") (pinfunction "2_2") (pintype "passive"))
    )
    (net (code "41") (name "Net-(U100-PA13{slash}COM2_1{slash}COM4_1)") (class "Default")
      (node (ref "U100") (pin "22") (pinfunction "PA13/COM2_1/COM4_1_22") (pintype "bidirectional"))
      (node (ref "X101") (pin "3") (pinfunction "3_3") (pintype "passive"))
    )
    (net (code "42") (name "Net-(U100-PA14{slash}COM2_2{slash}COM4_2{slash}XIN)") (class "Default")
      (node (ref "C100") (pin "1") (pinfunction "1_1") (pintype "passive"))
      (node (ref "U100") (pin "23") (pinfunction "PA14/COM2_2/COM4_2/XIN_23") (pintype "passive"))
      (node (ref "V100") (pin "2") (pinfunction "2_2") (pintype "passive"))
    )
    (net (code "43") (name "Net-(U100-PA15{slash}COM2_3{slash}COM4_3{slash}XOUT)") (class "Default")
      (node (ref "C102") (pin "1") (pinfunction "1_1") (pintype "passive"))
      (node (ref "U100") (pin "24") (pinfunction "PA15/COM2_3/COM4_3/XOUT_24") (pintype "passive"))
      (node (ref "V100") (pin "1") (pinfunction "1_1") (pintype "passive"))
    )
    (net (code "44") (name "Net-(U100-PA18{slash}COM1_2{slash}COM3_2)") (class "Default")
      (node (ref "D102") (pin "2") (pinfunction "2_2") (pintype "passive"))
      (node (ref "U100") (pin "27") (pinfunction "PA18/COM1_2/COM3_2_27") (pintype "bidirectional"))
    )
    (net (code "45") (name "Net-(U100-PA19{slash}COM1_3{slash}COM3_3)") (class "Default")
      (node (ref "D103") (pin "2") (pinfunction "2_2") (pintype "passive"))
      (node (ref "U100") (pin "28") (pinfunction "PA19/COM1_3/COM3_3_28") (pintype "bidirectional"))
    )
    (net (code "46") (name "Net-(U100-PA20{slash}COM5_2{slash}COM3_2)") (class "Default")
      (node (ref "D104") (pin "2") (pinfunction "2_2") (pintype "passive"))
      (node (ref "U100") (pin "29") (pinfunction "PA20/COM5_2/COM3_2_29") (pintype "bidirectional"))
    )
    (net (code "47") (name "Net-(U100-PA21{slash}COM5_3{slash}COM3_3)") (class "Default")
      (node (ref "D105") (pin "2") (pinfunction "2_2") (pintype "passive"))
      (node (ref "U100") (pin "30") (pinfunction "PA21/COM5_3/COM3_3_30") (pintype "bidirectional"))
    )
    (net (code "48") (name "Net-(U100-PA27)") (class "Default")
      (node (ref "R110") (pin "2") (pinfunction "2_2") (pintype "passive"))
      (node (ref "U100") (pin "39") (pinfunction "PA27_39") (pintype "bidirectional"))
    )
    (net (code "49") (name "Net-(U100-PA28)") (class "Default")
      (node (ref "R111") (pin "2") (pinfunction "2_2") (pintype "passive"))
      (node (ref "U100") (pin "41") (pinfunction "PA28_41") (pintype "bidirectional"))
    )
    (net (code "50") (name "Net-(U100-PB02{slash}COM5.0)") (class "Default")
      (node (ref "R112") (pin "2") (pinfunction "2_2") (pintype "passive"))
      (node (ref "U100") (pin "47") (pinfunction "PB02/COM5.0_47") (pintype "bidirectional"))
    )
    (net (code "51") (name "Net-(U100-PB03{slash}COM5.1)") (class "Default")
      (node (ref "R113") (pin "2") (pinfunction "2_2") (pintype "passive"))
      (node (ref "U100") (pin "48") (pinfunction "PB03/COM5.1_48") (pintype "bidirectional"))
    )
    (net (code "52") (name "Net-(U100-VDDCORE)") (class "Default")
      (node (ref "C112") (pin "2") (pinfunction "2_2") (pintype "passive"))
      (node (ref "C113") (pin "2") (pinfunction "2_2") (pintype "passive"))
      (node (ref "U100") (pin "43") (pinfunction "VDDCORE_43") (pintype "passive"))
    )
    (net (code "53") (name "Net-(U102-EN)") (class "Default")
      (node (ref "R104") (pin "1") (pinfunction "1_1") (pintype "passive"))
      (node (ref "U102") (pin "1") (pinfunction "EN_1") (pintype "passive"))
    )
    (net (code "54") (name "Net-(U103-+Vin)") (class "Default")
      (node (ref "L103") (pin "2") (pinfunction "2_2") (pintype "passive"))
      (node (ref "U103") (pin "1") (pinfunction "+Vin_1") (pintype "power_in"))
    )
    (net (code "55") (name "Net-(U103-+Vout)") (class "Default")
      (node (ref "L102") (pin "1") (pinfunction "1_1") (pintype "passive"))
      (node (ref "U103") (pin "6") (pinfunction "+Vout_6") (pintype "power_in"))
    )
    (net (code "56") (name "Net-(U104-A)") (class "Default")
      (node (ref "R114") (pin "2") (pinfunction "2_2") (pintype "passive"))
      (node (ref "U104") (pin "1") (pinfunction "A_1") (pintype "passive"))
    )
    (net (code "57") (name "Net-(U104-C-Pad4)") (class "Default")
      (node (ref "U104") (pin "4") (pinfunction "C_4") (pintype "passive"))
      (node (ref "V101") (pin "1") (pinfunction "1_1") (pintype "passive"))
    )
    (net (code "58") (name "Net-(U105-RxD)") (class "Default")
      (node (ref "R115") (pin "2") (pinfunction "2_2") (pintype "passive"))
      (node (ref "U105") (pin "1") (pinfunction "RxD_1") (pintype "open_collector"))
      (node (ref "U106") (pin "7") (pinfunction "INA_7") (pintype "input"))
    )
    (net (code "59") (name "Net-(U105-TxD)") (class "Default")
      (node (ref "U105") (pin "4") (pinfunction "TxD_4") (pintype "input"))
      (node (ref "U106") (pin "6") (pinfunction "OUTB_6") (pintype "output"))
    )
    (net (code "60") (name "Net-(U107-RxD)") (class "Default")
      (node (ref "R117") (pin "2") (pinfunction "2_2") (pintype "passive"))
      (node (ref "U107") (pin "1") (pinfunction "RxD_1") (pintype "open_collector"))
      (node (ref "U109") (pin "7") (pinfunction "INA_7") (pintype "input"))
    )
    (net (code "61") (name "Net-(U107-TxD)") (class "Default")
      (node (ref "U107") (pin "4") (pinfunction "TxD_4") (pintype "input"))
      (node (ref "U109") (pin "6") (pinfunction "OUTB_6") (pintype "output"))
    )
    (net (code "62") (name "Net-(U108-A)") (class "Default")
      (node (ref "R122") (pin "2") (pinfunction "2_2") (pintype "passive"))
      (node (ref "U108") (pin "1") (pinfunction "A_1") (pintype "passive"))
    )
    (net (code "63") (name "Net-(U108-C-Pad4)") (class "Default")
      (node (ref "U108") (pin "4") (pinfunction "C_4") (pintype "passive"))
      (node (ref "V102") (pin "1") (pinfunction "1_1") (pintype "passive"))
    )
    (net (code "64") (name "Net-(X100-Shield)") (class "Default")
      (node (ref "R101") (pin "2") (pinfunction "2_2") (pintype "passive"))
      (node (ref "X100") (pin "Shell") (pinfunction "Shield_Shell") (pintype "passive"))
    )
    (net (code "65") (name "unconnected-(U100-PA03{slash}AIN0_1{slash}VREFA-Pad4)") (class "Default")
      (node (ref "U100") (pin "4") (pinfunction "PA03/AIN0_1/VREFA_4") (pintype "bidirectional+no_connect"))
    )
    (net (code "66") (name "unconnected-(U100-PA04{slash}AIN0_4{slash}VREFB{slash}COM0_0-Pad9)") (class "Default")
      (node (ref "U100") (pin "9") (pinfunction "PA04/AIN0_4/VREFB/COM0_0_9") (pintype "bidirectional+no_connect"))
    )
    (net (code "67") (name "unconnected-(U100-PA05{slash}AIN0_5{slash}COM0_1-Pad10)") (class "Default")
      (node (ref "U100") (pin "10") (pinfunction "PA05/AIN0_5/COM0_1_10") (pintype "bidirectional+no_connect"))
    )
    (net (code "68") (name "unconnected-(U100-PA06{slash}AIN0_6{slash}COM0_2-Pad11)") (class "Default")
      (node (ref "U100") (pin "11") (pinfunction "PA06/AIN0_6/COM0_2_11") (pintype "bidirectional+no_connect"))
    )
    (net (code "69") (name "unconnected-(U100-PA16{slash}COM1_0{slash}COM3_0-Pad25)") (class "Default")
      (node (ref "U100") (pin "25") (pinfunction "PA16/COM1_0/COM3_0_25") (pintype "bidirectional+no_connect"))
    )
    (net (code "70") (name "unconnected-(U100-PA17{slash}COM1_1{slash}COM3_1-Pad26)") (class "Default")
      (node (ref "U100") (pin "26") (pinfunction "PA17/COM1_1/COM3_1_26") (pintype "bidirectional+no_connect"))
    )
    (net (code "71") (name "unconnected-(U100-PA22{slash}COM3_0{slash}COM5_0-Pad31)") (class "Default")
      (node (ref "U100") (pin "31") (pinfunction "PA22/COM3_0/COM5_0_31") (pintype "bidirectional+no_connect"))
    )
    (net (code "72") (name "unconnected-(U100-PA23{slash}COM3_1{slash}COM5_1-Pad32)") (class "Default")
      (node (ref "U100") (pin "32") (pinfunction "PA23/COM3_1/COM5_1_32") (pintype "bidirectional+no_connect"))
    )
    (net (code "73") (name "unconnected-(U100-PB09{slash}AIN0_3{slash}COM4_1-Pad8)") (class "Default")
      (node (ref "U100") (pin "8") (pinfunction "PB09/AIN0_3/COM4_1_8") (pintype "bidirectional+no_connect"))
    )
    (net (code "74") (name "unconnected-(U100-PB10{slash}COM4_2-Pad19)") (class "Default")
      (node (ref "U100") (pin "19") (pinfunction "PB10/COM4_2_19") (pintype "bidirectional+no_connect"))
    )
    (net (code "75") (name "unconnected-(U100-PB11{slash}COM4_3-Pad20)") (class "Default")
      (node (ref "U100") (pin "20") (pinfunction "PB11/COM4_3_20") (pintype "bidirectional+no_connect"))
    )
    (net (code "76") (name "unconnected-(U100-PB22{slash}COM5_2-Pad37)") (class "Default")
      (node (ref "U100") (pin "37") (pinfunction "PB22/COM5_2_37") (pintype "bidirectional+no_connect"))
    )
    (net (code "77") (name "unconnected-(U100-PB23{slash}COM5_3-Pad38)") (class "Default")
      (node (ref "U100") (pin "38") (pinfunction "PB23/COM5_3_38") (pintype "bidirectional+no_connect"))
    )
    (net (code "78") (name "unconnected-(U105-NC-Pad3)") (class "Default")
      (node (ref "U105") (pin "3") (pinfunction "NC_3") (pintype "passive+no_connect"))
    )
    (net (code "79") (name "unconnected-(U105-NC-Pad8)") (class "Default")
      (node (ref "U105") (pin "8") (pinfunction "NC_8") (pintype "passive+no_connect"))
    )
    (net (code "80") (name "unconnected-(U107-NC-Pad3)") (class "Default")
      (node (ref "U107") (pin "3") (pinfunction "NC_3") (pintype "passive+no_connect"))
    )
    (net (code "81") (name "unconnected-(U107-NC-Pad8)") (class "Default")
      (node (ref "U107") (pin "8") (pinfunction "NC_8") (pintype "passive+no_connect"))
    )
    (net (code "82") (name "unconnected-(X102-Pad1)") (class "Default")
      (node (ref "X102") (pin "1") (pinfunction "1_1") (pintype "passive"))
    )
    (net (code "83") (name "unconnected-(X102-Pad2)") (class "Default")
      (node (ref "X102") (pin "2") (pinfunction "2_2") (pintype "passive"))
    )
    (net (code "84") (name "unconnected-(X102-Pad4)") (class "Default")
      (node (ref "X102") (pin "4") (pinfunction "4_4") (pintype "passive"))
    )
    (net (code "85") (name "unconnected-(X102-Pad5)") (class "Default")
      (node (ref "X102") (pin "5") (pinfunction "5_5") (pintype "passive"))
    )
    (net (code "86") (name "unconnected-(X102-Pad9)") (class "Default")
      (node (ref "X102") (pin "9") (pinfunction "9_9") (pintype "passive"))
    )
    (net (code "87") (name "unconnected-(X102-PadSH)") (class "Default")
      (node (ref "X102") (pin "SH") (pinfunction "SH_SH") (pintype "passive"))
    )
    (net (code "88") (name "unconnected-(X103-KEY-Pad7)") (class "Default")
      (node (ref "X103") (pin "7") (pinfunction "KEY_7") (pintype "passive"))
    )
    (net (code "89") (name "unconnected-(X103-NC{slash}TDI-Pad8)") (class "Default")
      (node (ref "X103") (pin "8") (pinfunction "NC/TDI_8") (pintype "passive"))
    )
    (net (code "90") (name "unconnected-(X103-SWO{slash}TDO-Pad6)") (class "Default")
      (node (ref "X103") (pin "6") (pinfunction "SWO/TDO_6") (pintype "passive"))
    )
  )
)
